# beacon_1551G.net
KiCad netlist of a schematic drawn in EAGLE
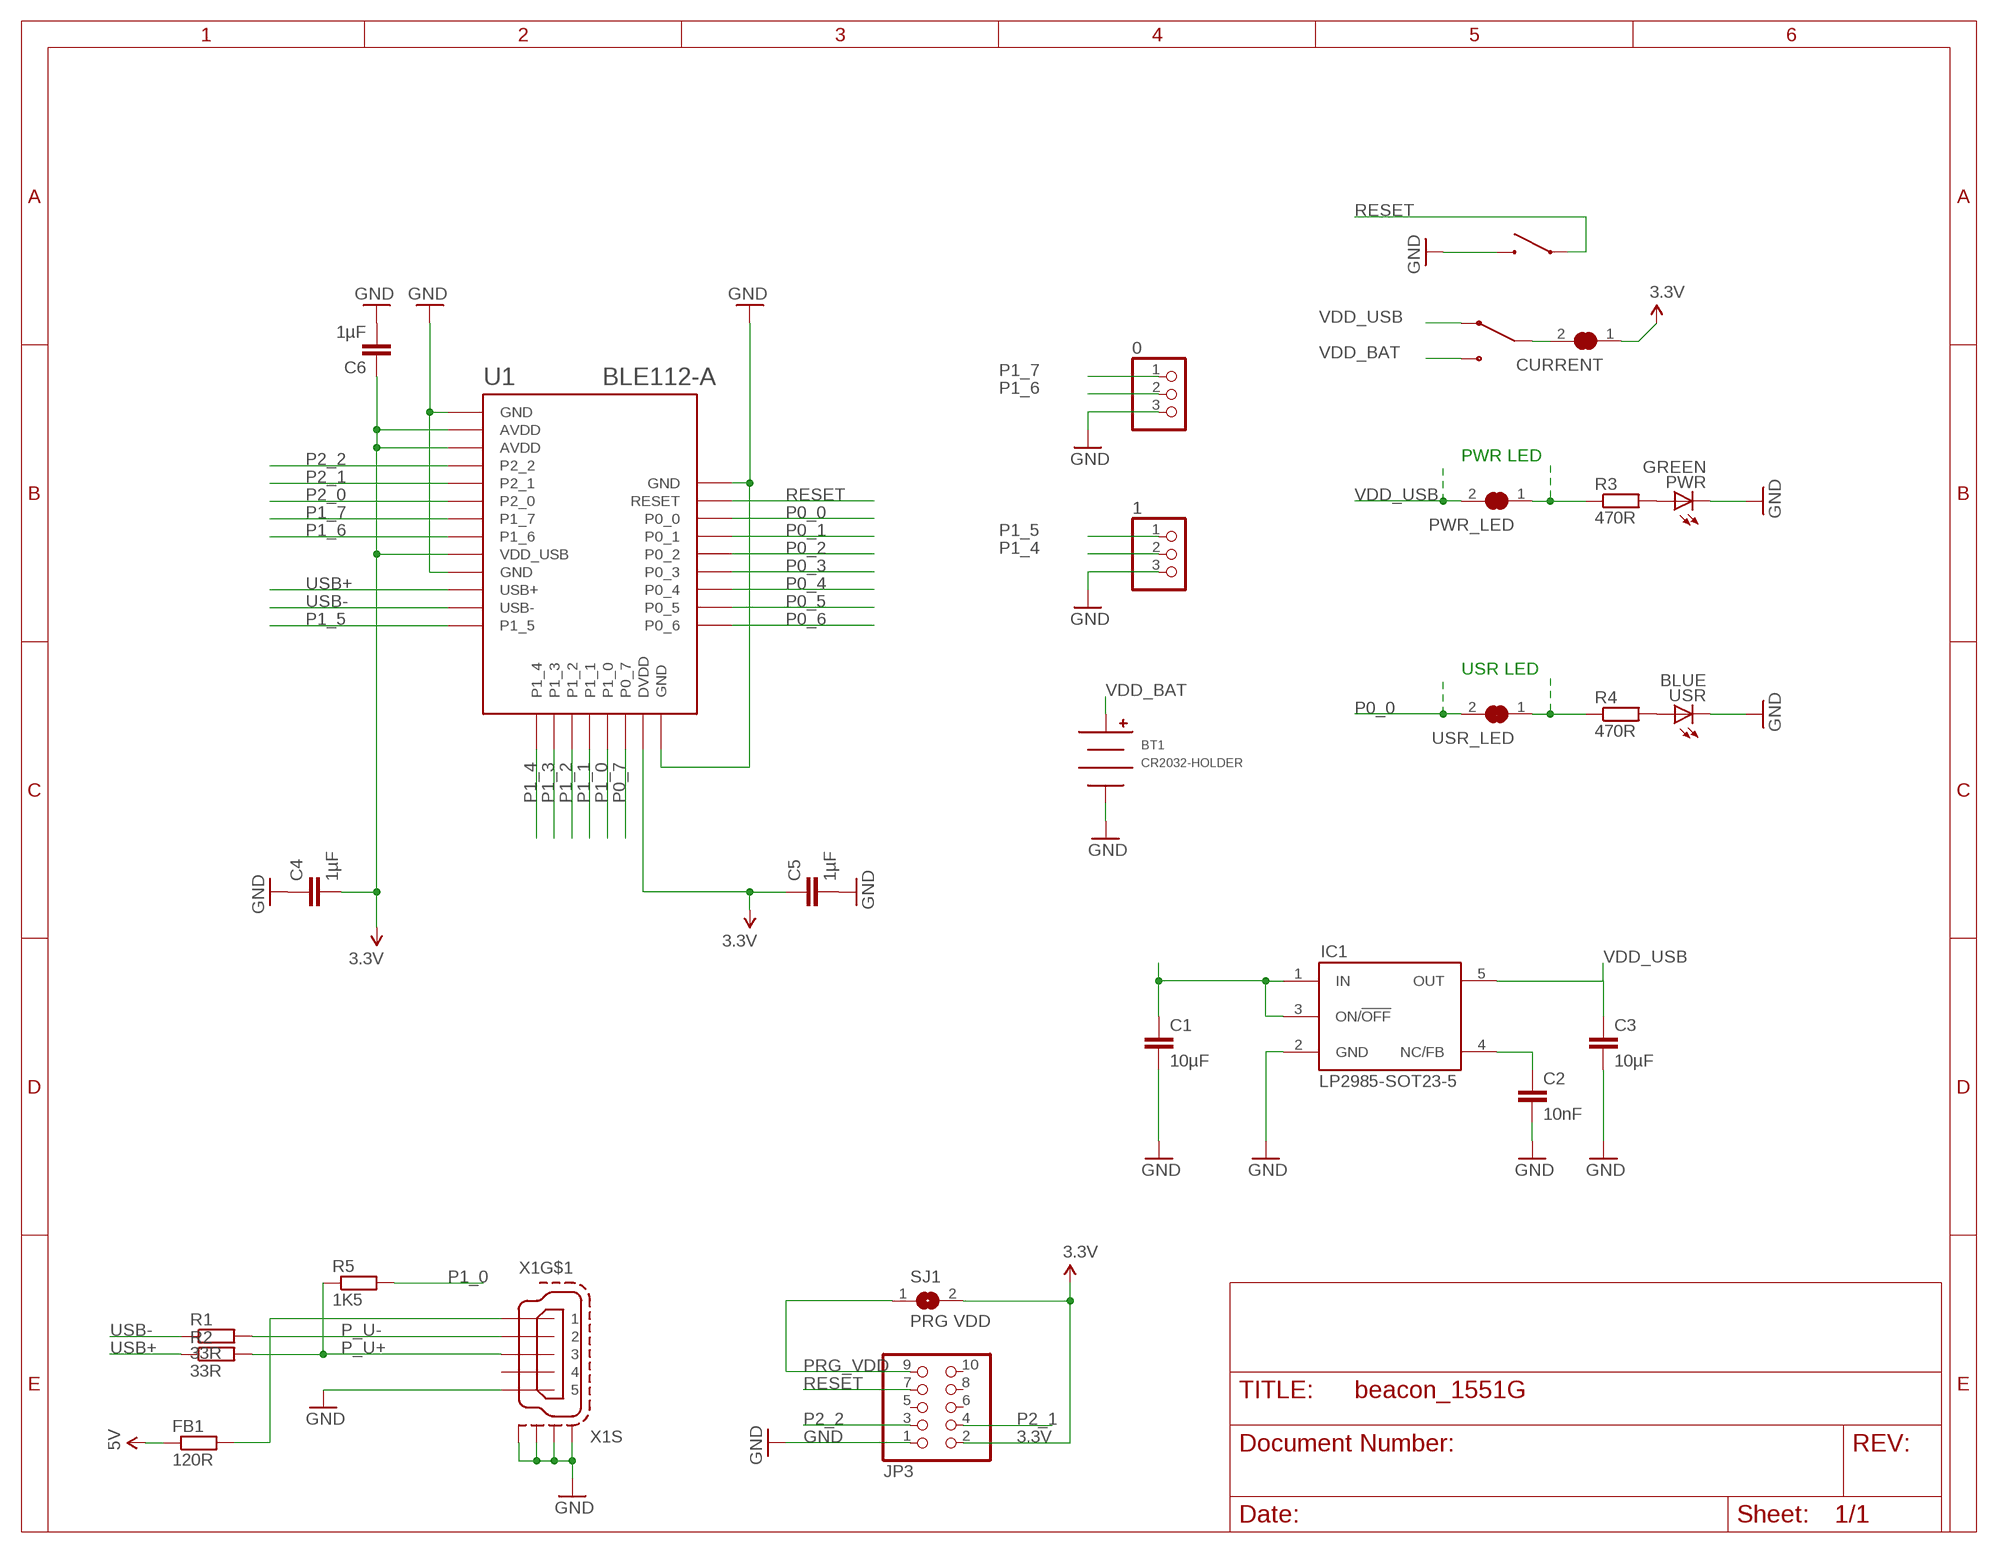
[diagram p0: schematic, sheet 1]

(export (version "E")
  (design (tool "Eeschema 10.0.6"))
  (components
    (comp (ref "0")
      (value "HEADER-1X3ROUND")
      (footprint "eagle-import:1X03_ROUND")
      (libsource (lib "eagle-import") (part "HEADER-1X3ROUND"))
    )
    (comp (ref "1")
      (value "HEADER-1X3ROUND")
      (footprint "eagle-import:1X03_ROUND")
      (libsource (lib "eagle-import") (part "HEADER-1X3ROUND"))
    )
    (comp (ref "BT1")
      (value "CR2032-HOLDER")
      (footprint "eagle-import:CH28-2032LF")
      (libsource (lib "eagle-import") (part "CR2032-HOLDER"))
    )
    (comp (ref "C1")
      (value "10µF")
      (footprint "eagle-import:C0603")
      (libsource (lib "eagle-import") (part "C-EUC0603"))
    )
    (comp (ref "C2")
      (value "10nF")
      (footprint "eagle-import:C0603")
      (libsource (lib "eagle-import") (part "C-EUC0603"))
    )
    (comp (ref "C3")
      (value "10µF")
      (footprint "eagle-import:C0603")
      (libsource (lib "eagle-import") (part "C-EUC0603"))
    )
    (comp (ref "C4")
      (value "1µF")
      (footprint "eagle-import:C0603")
      (libsource (lib "eagle-import") (part "C-EUC0603"))
    )
    (comp (ref "C5")
      (value "1µF")
      (footprint "eagle-import:C0603")
      (libsource (lib "eagle-import") (part "C-EUC0603"))
    )
    (comp (ref "C6")
      (value "1µF")
      (footprint "eagle-import:C0603")
      (libsource (lib "eagle-import") (part "C-EUC0603"))
    )
    (comp (ref "CURRENT")
      (value "SOLDERJUMPER_CLOSED")
      (footprint "eagle-import:SOLDERJUMPER_CLOSEDWIRE")
      (libsource (lib "eagle-import") (part "SOLDERJUMPER_CLOSED"))
    )
    (comp (ref "FB1")
      (value "120R")
      (footprint "eagle-import:R0603")
      (libsource (lib "eagle-import") (part "R-EU_R0603"))
    )
    (comp (ref "IC1")
      (value "LP2985-SOT23-5")
      (footprint "eagle-import:SOT23-5")
      (libsource (lib "eagle-import") (part "LP2985-SOT23-5"))
    )
    (comp (ref "JP3")
      (value "ARM-JTAG_1.27-SMD")
      (footprint "eagle-import:20021121-10010XXLF")
      (libsource (lib "eagle-import") (part "ARM-JTAG_1.27-SMD"))
    )
    (comp (ref "PWR")
      (value "GREEN")
      (footprint "eagle-import:CHIPLED_0805")
      (libsource (lib "eagle-import") (part "LEDCHIPLED_0805"))
    )
    (comp (ref "PWR_LED")
      (value "SOLDERJUMPER_CLOSED")
      (footprint "eagle-import:SOLDERJUMPER_CLOSEDWIRE")
      (libsource (lib "eagle-import") (part "SOLDERJUMPER_CLOSED"))
    )
    (comp (ref "R1")
      (value "33R")
      (footprint "eagle-import:R0603")
      (libsource (lib "eagle-import") (part "R-EU_R0603"))
    )
    (comp (ref "R2")
      (value "33R")
      (footprint "eagle-import:R0603")
      (libsource (lib "eagle-import") (part "R-EU_R0603"))
    )
    (comp (ref "R3")
      (value "470R")
      (footprint "eagle-import:R0603")
      (libsource (lib "eagle-import") (part "R-EU_R0603"))
    )
    (comp (ref "R4")
      (value "470R")
      (footprint "eagle-import:R0603")
      (libsource (lib "eagle-import") (part "R-EU_R0603"))
    )
    (comp (ref "R5")
      (value "1K5")
      (footprint "eagle-import:R0603")
      (libsource (lib "eagle-import") (part "R-EU_R0603"))
    )
    (comp (ref "RST")
      (value "TACT-SWITCH-40-40")
      (footprint "eagle-import:40-40")
      (libsource (lib "eagle-import") (part "TACT-SWITCH-40-40"))
    )
    (comp (ref "SJ1")
      (value "PRG VDD")
      (footprint "eagle-import:SJ")
      (libsource (lib "eagle-import") (part "SJ"))
    )
    (comp (ref "U$1")
      (value "1P2T")
      (footprint "eagle-import:1P2T-ON-ON")
      (libsource (lib "eagle-import") (part "1P2T"))
    )
    (comp (ref "U1")
      (value "BLE112-A")
      (footprint "eagle-import:BLE112-A")
      (libsource (lib "eagle-import") (part "BLE112-A-VISUAL"))
    )
    (comp (ref "USR")
      (value "BLUE")
      (footprint "eagle-import:CHIPLED_0805")
      (libsource (lib "eagle-import") (part "LEDCHIPLED_0805"))
    )
    (comp (ref "USR_LED")
      (value "SOLDERJUMPER_CLOSED")
      (footprint "eagle-import:SOLDERJUMPER_CLOSEDWIRE")
      (libsource (lib "eagle-import") (part "SOLDERJUMPER_CLOSED"))
    )
    (comp (ref "X1")
      (value "MINI-USB-SCHIELD-32005-301")
      (footprint "eagle-import:32005-301")
      (libsource (lib "eagle-import") (part "MINI-USB-SCHIELD-32005-301"))
    )
  )
  (nets
    (net (code "1") (name "/P0_0") (class "Default")
      (node (ref "U1") (pin "P0_0") (pinfunction "P0_0_P0_0") (pintype "bidirectional"))
      (node (ref "USR_LED") (pin "2") (pinfunction "2_2") (pintype "passive"))
    )
    (net (code "2") (name "/P0_1") (class "Default")
      (node (ref "U1") (pin "P0_1") (pinfunction "P0_1_P0_1") (pintype "bidirectional"))
    )
    (net (code "3") (name "/P0_2") (class "Default")
      (node (ref "U1") (pin "P0_2") (pinfunction "P0_2_P0_2") (pintype "bidirectional"))
    )
    (net (code "4") (name "/P0_3") (class "Default")
      (node (ref "U1") (pin "P0_3") (pinfunction "P0_3_P0_3") (pintype "bidirectional"))
    )
    (net (code "5") (name "/P0_4") (class "Default")
      (node (ref "U1") (pin "P0_4") (pinfunction "P0_4_P0_4") (pintype "bidirectional"))
    )
    (net (code "6") (name "/P0_5") (class "Default")
      (node (ref "U1") (pin "P0_5") (pinfunction "P0_5_P0_5") (pintype "bidirectional"))
    )
    (net (code "7") (name "/P0_6") (class "Default")
      (node (ref "U1") (pin "P0_6") (pinfunction "P0_6_P0_6") (pintype "bidirectional"))
    )
    (net (code "8") (name "/P0_7") (class "Default")
      (node (ref "U1") (pin "P0_7") (pinfunction "P0_7_P0_7") (pintype "bidirectional"))
    )
    (net (code "9") (name "/P1_0") (class "Default")
      (node (ref "R5") (pin "2") (pinfunction "2_2") (pintype "passive"))
      (node (ref "U1") (pin "P1_0") (pinfunction "P1_0_P1_0") (pintype "bidirectional"))
    )
    (net (code "10") (name "/P1_1") (class "Default")
      (node (ref "U1") (pin "P1_1") (pinfunction "P1_1_P1_1") (pintype "bidirectional"))
    )
    (net (code "11") (name "/P1_2") (class "Default")
      (node (ref "U1") (pin "P1_2") (pinfunction "P1_2_P1_2") (pintype "bidirectional"))
    )
    (net (code "12") (name "/P1_3") (class "Default")
      (node (ref "U1") (pin "P1_3") (pinfunction "P1_3_P1_3") (pintype "bidirectional"))
    )
    (net (code "13") (name "/P1_4") (class "Default")
      (node (ref "1") (pin "2") (pinfunction "2_2") (pintype "passive"))
      (node (ref "U1") (pin "P1_4") (pinfunction "P1_4_P1_4") (pintype "bidirectional"))
    )
    (net (code "14") (name "/P1_5") (class "Default")
      (node (ref "1") (pin "1") (pinfunction "1_1") (pintype "passive"))
      (node (ref "U1") (pin "P1_5") (pinfunction "P1_5_P1_5") (pintype "bidirectional"))
    )
    (net (code "15") (name "/P1_6") (class "Default")
      (node (ref "0") (pin "2") (pinfunction "2_2") (pintype "passive"))
      (node (ref "U1") (pin "P1_6") (pinfunction "P1_6_P1_6") (pintype "bidirectional"))
    )
    (net (code "16") (name "/P1_7") (class "Default")
      (node (ref "0") (pin "1") (pinfunction "1_1") (pintype "passive"))
      (node (ref "U1") (pin "P1_7") (pinfunction "P1_7_P1_7") (pintype "bidirectional"))
    )
    (net (code "17") (name "/P2_0") (class "Default")
      (node (ref "U1") (pin "P2_0") (pinfunction "P2_0_P2_0") (pintype "bidirectional"))
    )
    (net (code "18") (name "/P2_1") (class "Default")
      (node (ref "JP3") (pin "4") (pinfunction "4_4") (pintype "passive"))
      (node (ref "U1") (pin "P2_1") (pinfunction "P2_1_P2_1") (pintype "bidirectional"))
    )
    (net (code "19") (name "/P2_2") (class "Default")
      (node (ref "JP3") (pin "3") (pinfunction "3_3") (pintype "passive"))
      (node (ref "U1") (pin "P2_2") (pinfunction "P2_2_P2_2") (pintype "bidirectional"))
    )
    (net (code "20") (name "/PRG_VDD") (class "Default")
      (node (ref "JP3") (pin "9") (pinfunction "9_9") (pintype "passive"))
      (node (ref "SJ1") (pin "1") (pinfunction "1_1") (pintype "passive"))
    )
    (net (code "21") (name "/P_U+") (class "Default")
      (node (ref "R2") (pin "2") (pinfunction "2_2") (pintype "passive"))
      (node (ref "R5") (pin "1") (pinfunction "1_1") (pintype "passive"))
      (node (ref "X1") (pin "3") (pinfunction "3_3") (pintype "passive"))
    )
    (net (code "22") (name "/P_U-") (class "Default")
      (node (ref "R1") (pin "2") (pinfunction "2_2") (pintype "passive"))
      (node (ref "X1") (pin "2") (pinfunction "2_2") (pintype "passive"))
    )
    (net (code "23") (name "/RESET") (class "Default")
      (node (ref "JP3") (pin "7") (pinfunction "7_7") (pintype "passive"))
      (node (ref "RST") (pin "3") (pinfunction "P$2_3") (pintype "bidirectional"))
      (node (ref "RST") (pin "4") (pinfunction "P$2_4") (pintype "bidirectional"))
      (node (ref "U1") (pin "RESET") (pinfunction "RESET_RESET") (pintype "input"))
    )
    (net (code "24") (name "/USB+") (class "Default")
      (node (ref "R2") (pin "1") (pinfunction "1_1") (pintype "passive"))
      (node (ref "U1") (pin "USB+") (pinfunction "USB+_USB+") (pintype "bidirectional"))
    )
    (net (code "25") (name "/USB-") (class "Default")
      (node (ref "R1") (pin "1") (pinfunction "1_1") (pintype "passive"))
      (node (ref "U1") (pin "USB-") (pinfunction "USB-_USB-") (pintype "bidirectional"))
    )
    (net (code "26") (name "/VDD_BAT") (class "Default")
      (node (ref "BT1") (pin "POS") (pinfunction "POS_POS") (pintype "bidirectional"))
      (node (ref "U$1") (pin "3") (pinfunction "P$3_3") (pintype "bidirectional"))
    )
    (net (code "27") (name "/VDD_USB") (class "Default")
      (node (ref "C3") (pin "1") (pinfunction "1_1") (pintype "passive"))
      (node (ref "IC1") (pin "5") (pinfunction "OUT_5") (pintype "bidirectional"))
      (node (ref "PWR_LED") (pin "2") (pinfunction "2_2") (pintype "passive"))
      (node (ref "U$1") (pin "1") (pinfunction "P$1_1") (pintype "bidirectional"))
    )
    (net (code "28") (name "3.3V") (class "Default")
      (node (ref "C4") (pin "2") (pinfunction "2_2") (pintype "passive"))
      (node (ref "C5") (pin "1") (pinfunction "1_1") (pintype "passive"))
      (node (ref "C6") (pin "1") (pinfunction "1_1") (pintype "passive"))
      (node (ref "CURRENT") (pin "1") (pinfunction "1_1") (pintype "passive"))
      (node (ref "JP3") (pin "2") (pinfunction "2_2") (pintype "passive"))
      (node (ref "SJ1") (pin "2") (pinfunction "2_2") (pintype "passive"))
      (node (ref "U1") (pin "AVDD1") (pinfunction "AVDD_AVDD1") (pintype "power_in"))
      (node (ref "U1") (pin "AVDD2") (pinfunction "AVDD_AVDD2") (pintype "power_in"))
      (node (ref "U1") (pin "DVDD") (pinfunction "DVDD_DVDD") (pintype "power_in"))
      (node (ref "U1") (pin "VDD_USB") (pinfunction "VDD_USB_VDD_USB") (pintype "power_in"))
    )
    (net (code "29") (name "5V") (class "Default")
      (node (ref "FB1") (pin "1") (pinfunction "1_1") (pintype "passive"))
    )
    (net (code "30") (name "GND") (class "Default")
      (node (ref "0") (pin "3") (pinfunction "3_3") (pintype "passive"))
      (node (ref "1") (pin "3") (pinfunction "3_3") (pintype "passive"))
      (node (ref "BT1") (pin "NEG") (pinfunction "NEG_NEG") (pintype "bidirectional"))
      (node (ref "C1") (pin "2") (pinfunction "2_2") (pintype "passive"))
      (node (ref "C2") (pin "2") (pinfunction "2_2") (pintype "passive"))
      (node (ref "C3") (pin "2") (pinfunction "2_2") (pintype "passive"))
      (node (ref "C4") (pin "1") (pinfunction "1_1") (pintype "passive"))
      (node (ref "C5") (pin "2") (pinfunction "2_2") (pintype "passive"))
      (node (ref "C6") (pin "2") (pinfunction "2_2") (pintype "passive"))
      (node (ref "IC1") (pin "2") (pinfunction "GND_2") (pintype "bidirectional"))
      (node (ref "JP3") (pin "1") (pinfunction "1_1") (pintype "passive"))
      (node (ref "PWR") (pin "C") (pinfunction "C_C") (pintype "passive"))
      (node (ref "RST") (pin "1") (pinfunction "P$1_1") (pintype "bidirectional"))
      (node (ref "RST") (pin "2") (pinfunction "P$1_2") (pintype "bidirectional"))
      (node (ref "U1") (pin "GND1") (pinfunction "GND_GND1") (pintype "power_in"))
      (node (ref "U1") (pin "GND2") (pinfunction "GND_GND2") (pintype "power_in"))
      (node (ref "U1") (pin "GND3") (pinfunction "GND_GND3") (pintype "power_in"))
      (node (ref "U1") (pin "GND4") (pinfunction "GND_GND4") (pintype "power_in"))
      (node (ref "USR") (pin "C") (pinfunction "C_C") (pintype "passive"))
      (node (ref "X1") (pin "5") (pinfunction "5_5") (pintype "passive"))
      (node (ref "X1") (pin "M1") (pinfunction "S1_M1") (pintype "passive"))
      (node (ref "X1") (pin "M2") (pinfunction "S2_M2") (pintype "passive"))
      (node (ref "X1") (pin "M3") (pinfunction "S3_M3") (pintype "passive"))
      (node (ref "X1") (pin "M4") (pinfunction "S4_M4") (pintype "passive"))
    )
    (net (code "31") (name "Net-(FB1-Pad2)") (class "Default")
      (node (ref "FB1") (pin "2") (pinfunction "2_2") (pintype "passive"))
      (node (ref "X1") (pin "1") (pinfunction "1_1") (pintype "passive"))
    )
    (net (code "32") (name "Net-(IC1-IN)") (class "Default")
      (node (ref "C1") (pin "1") (pinfunction "1_1") (pintype "passive"))
      (node (ref "IC1") (pin "1") (pinfunction "IN_1") (pintype "bidirectional"))
      (node (ref "IC1") (pin "3") (pinfunction "ON/~{OFF}_3") (pintype "bidirectional"))
    )
    (net (code "33") (name "Net-(IC1-NC{slash}FB)") (class "Default")
      (node (ref "C2") (pin "1") (pinfunction "1_1") (pintype "passive"))
      (node (ref "IC1") (pin "4") (pinfunction "NC/FB_4") (pintype "bidirectional"))
    )
    (net (code "34") (name "Net-(PWR-PadA)") (class "Default")
      (node (ref "PWR") (pin "A") (pinfunction "A_A") (pintype "passive"))
      (node (ref "R3") (pin "2") (pinfunction "2_2") (pintype "passive"))
    )
    (net (code "35") (name "Net-(PWR_LED-Pad1)") (class "Default")
      (node (ref "PWR_LED") (pin "1") (pinfunction "1_1") (pintype "passive"))
      (node (ref "R3") (pin "1") (pinfunction "1_1") (pintype "passive"))
    )
    (net (code "36") (name "Net-(R4-Pad1)") (class "Default")
      (node (ref "R4") (pin "1") (pinfunction "1_1") (pintype "passive"))
      (node (ref "USR_LED") (pin "1") (pinfunction "1_1") (pintype "passive"))
    )
    (net (code "37") (name "Net-(R4-Pad2)") (class "Default")
      (node (ref "R4") (pin "2") (pinfunction "2_2") (pintype "passive"))
      (node (ref "USR") (pin "A") (pinfunction "A_A") (pintype "passive"))
    )
    (net (code "38") (name "Net-(U$1-P$2)") (class "Default")
      (node (ref "CURRENT") (pin "2") (pinfunction "2_2") (pintype "passive"))
      (node (ref "U$1") (pin "2") (pinfunction "P$2_2") (pintype "bidirectional"))
    )
    (net (code "39") (name "unconnected-(JP3-Pad5)") (class "Default")
      (node (ref "JP3") (pin "5") (pinfunction "5_5") (pintype "passive"))
    )
    (net (code "40") (name "unconnected-(JP3-Pad6)") (class "Default")
      (node (ref "JP3") (pin "6") (pinfunction "6_6") (pintype "passive"))
    )
    (net (code "41") (name "unconnected-(JP3-Pad8)") (class "Default")
      (node (ref "JP3") (pin "8") (pinfunction "8_8") (pintype "passive"))
    )
    (net (code "42") (name "unconnected-(JP3-Pad10)") (class "Default")
      (node (ref "JP3") (pin "10") (pinfunction "10_10") (pintype "passive"))
    )
    (net (code "43") (name "unconnected-(X1-Pad4)") (class "Default")
      (node (ref "X1") (pin "4") (pinfunction "4_4") (pintype "passive"))
    )
  )
)
